# Header.net
KiCad netlist of a schematic drawn in Altium Designer
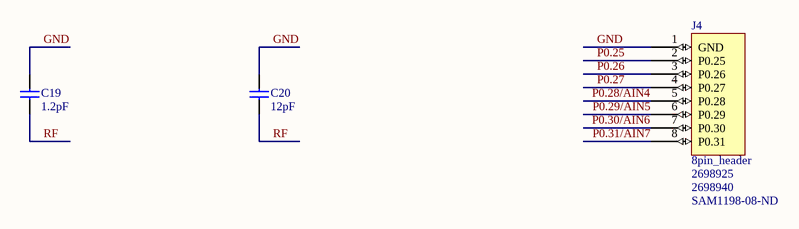
[diagram p0: Header.SchDoc]

(export (version "E")
  (design (tool "Eeschema 10.0.6"))
  (components
    (comp (ref "C19")
      (value "1.2pF")
      (footprint "CAPC1005X04L")
      (description "Capacitor, NP0, ±2%")
      (fields (field (name "PART NUMBER") "C0402-12p") (field (name "PUBLISHER") "Nordic Semiconductor"))
      (libsource (lib "nRF52832_Breakout_V2") (part "CAP"))
    )
    (comp (ref "C20")
      (value "12pF")
      (footprint "CAPC1005X04L")
      (description "Capacitor, NP0, ±2%")
      (fields (field (name "PART NUMBER") "C0402-12p") (field (name "PUBLISHER") "Nordic Semiconductor"))
      (libsource (lib "nRF52832_Breakout_V2") (part "CAP"))
    )
    (comp (ref "J4")
      (value "8pin_header")
      (footprint "SOCKET_1x8_SMD")
      (fields
        (field (name "SUPPLIER PART NUMBER 1") "2698925")
        (field (name "SUPPLIER PART NUMBER 2") "2698940")
        (field (name "SUPPLIER PART NUMBER 3") "SAM1198-08-ND")
      )
      (libsource (lib "nRF52832_Breakout_V2") (part "8pin_header"))
    )
  )
  (nets
    (net (code "1") (name "/GND") (class "Default")
      (node (ref "C19") (pin "2") (pinfunction "2_2") (pintype "passive"))
      (node (ref "C20") (pin "2") (pinfunction "2_2") (pintype "passive"))
      (node (ref "J4") (pin "1") (pinfunction "GND_1") (pintype "bidirectional"))
    )
    (net (code "2") (name "/P0.25") (class "Default")
      (node (ref "J4") (pin "2") (pinfunction "P0.25_2") (pintype "bidirectional"))
    )
    (net (code "3") (name "/P0.26") (class "Default")
      (node (ref "J4") (pin "3") (pinfunction "P0.26_3") (pintype "bidirectional"))
    )
    (net (code "4") (name "/P0.27") (class "Default")
      (node (ref "J4") (pin "4") (pinfunction "P0.27_4") (pintype "bidirectional"))
    )
    (net (code "5") (name "/P0.28{slash}AIN4") (class "Default")
      (node (ref "J4") (pin "5") (pinfunction "P0.28_5") (pintype "bidirectional"))
    )
    (net (code "6") (name "/P0.29{slash}AIN5") (class "Default")
      (node (ref "J4") (pin "6") (pinfunction "P0.29_6") (pintype "bidirectional"))
    )
    (net (code "7") (name "/P0.30{slash}AIN6") (class "Default")
      (node (ref "J4") (pin "7") (pinfunction "P0.30_7") (pintype "bidirectional"))
    )
    (net (code "8") (name "/P0.31{slash}AIN7") (class "Default")
      (node (ref "J4") (pin "8") (pinfunction "P0.31_8") (pintype "bidirectional"))
    )
    (net (code "9") (name "/RF") (class "Default")
      (node (ref "C19") (pin "1") (pinfunction "1_1") (pintype "passive"))
      (node (ref "C20") (pin "1") (pinfunction "1_1") (pintype "passive"))
    )
  )
)
